# ControlBoardV2_PRO.net
KiCad netlist of a schematic drawn in EAGLE
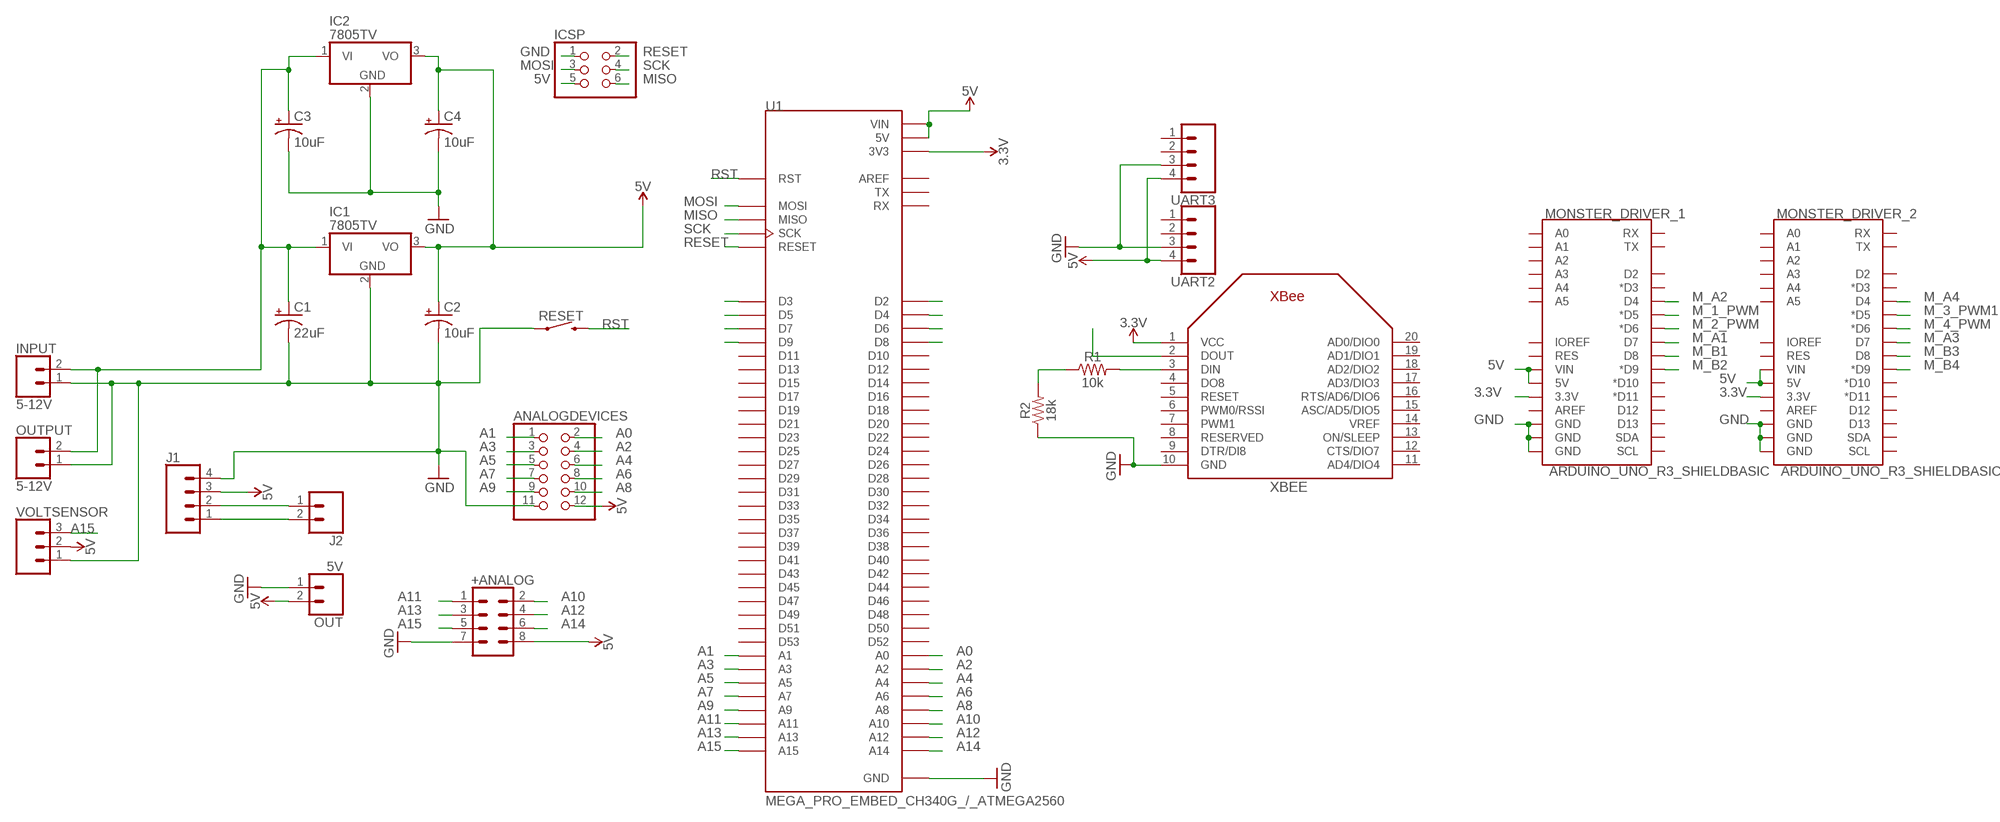
[diagram p0: schematic, sheet 1]

(export (version "E")
  (design (tool "Eeschema 10.0.6"))
  (components
    (comp (ref "+ANALOG")
      (value "CONN_04X2")
      (footprint "eagle-import:2X4")
      (libsource (lib "eagle-import") (part "CONN_04X2"))
    )
    (comp (ref "ANALOGDEVICES")
      (value "PINHD-2X6")
      (footprint "eagle-import:2X06")
      (libsource (lib "eagle-import") (part "PINHD-2X6"))
    )
    (comp (ref "C1")
      (value "22uF")
      (footprint "eagle-import:E2,5-5")
      (libsource (lib "eagle-import") (part "CPOL-USE2.5-5"))
    )
    (comp (ref "C2")
      (value "10uF")
      (footprint "eagle-import:E2,5-5")
      (libsource (lib "eagle-import") (part "CPOL-USE2.5-5"))
    )
    (comp (ref "C3")
      (value "10uF")
      (footprint "eagle-import:E2,5-5")
      (libsource (lib "eagle-import") (part "CPOL-USE2.5-5"))
    )
    (comp (ref "C4")
      (value "10uF")
      (footprint "eagle-import:E2,5-5")
      (libsource (lib "eagle-import") (part "CPOL-USE2.5-5"))
    )
    (comp (ref "IC1")
      (value "7805TV")
      (footprint "eagle-import:TO220V")
      (libsource (lib "eagle-import") (part "78TV05"))
    )
    (comp (ref "IC2")
      (value "7805TV")
      (footprint "eagle-import:TO220V")
      (libsource (lib "eagle-import") (part "78TV05"))
    )
    (comp (ref "ICSP")
      (value "PINHD-2X3")
      (footprint "eagle-import:2X03")
      (libsource (lib "eagle-import") (part "PINHD-2X3"))
    )
    (comp (ref "INPUT")
      (value "5-12V")
      (footprint "eagle-import:SCREWTERMINAL-3.5MM-2")
      (libsource (lib "eagle-import") (part "CONN_023.5MM"))
    )
    (comp (ref "J1")
      (value "CONN_04")
      (footprint "eagle-import:1X04")
      (libsource (lib "eagle-import") (part "CONN_04"))
    )
    (comp (ref "J2")
      (value "CONN_02")
      (footprint "eagle-import:1X02")
      (libsource (lib "eagle-import") (part "CONN_02"))
    )
    (comp (ref "MONSTER_DRIVER_1")
      (value "ARDUINO_UNO_R3_SHIELDBASIC")
      (footprint "eagle-import:UNO_R3_SHIELD")
      (libsource (lib "eagle-import") (part "ARDUINO_UNO_R3_SHIELDBASIC"))
    )
    (comp (ref "MONSTER_DRIVER_2")
      (value "ARDUINO_UNO_R3_SHIELDBASIC")
      (footprint "eagle-import:UNO_R3_SHIELD")
      (libsource (lib "eagle-import") (part "ARDUINO_UNO_R3_SHIELDBASIC"))
    )
    (comp (ref "OUT")
      (value "5V")
      (footprint "eagle-import:SCREWTERMINAL-3.5MM-2")
      (libsource (lib "eagle-import") (part "CONN_023.5MM"))
    )
    (comp (ref "OUTPUT")
      (value "5-12V")
      (footprint "eagle-import:SCREWTERMINAL-3.5MM-2")
      (libsource (lib "eagle-import") (part "CONN_023.5MM"))
    )
    (comp (ref "R1")
      (value "10k")
      (footprint "eagle-import:AXIAL-0.3")
      (libsource (lib "eagle-import") (part "10KOHM-HORIZ-1/4W-1%"))
    )
    (comp (ref "R2")
      (value "18k")
      (footprint "eagle-import:AXIAL-0.3")
      (libsource (lib "eagle-import") (part "10KOHM-HORIZ-1/4W-1%"))
    )
    (comp (ref "RESET")
      (value "MOMENTARY-SWITCH-SPST-PTH-6.0MM")
      (footprint "eagle-import:TACTILE_SWITCH_PTH_6.0MM")
      (libsource (lib "eagle-import") (part "MOMENTARY-SWITCH-SPST-PTH-6.0MM"))
    )
    (comp (ref "U1")
      (value "MEGA_PRO_EMBED_CH340G_/_ATMEGA2560")
      (footprint "eagle-import:MODULE_MEGA_PRO_EMBED_CH340G___ATMEGA2560")
      (fields (field (name "MF") "Robotdyn") (field (name "MP") "Mega Pro Embed CH340G / ATmega2560"))
      (libsource (lib "eagle-import") (part "MEGA_PRO_EMBED_CH340G_/_ATMEGA2560"))
    )
    (comp (ref "UART2")
      (value "CONN_04")
      (footprint "eagle-import:1X04")
      (libsource (lib "eagle-import") (part "CONN_04"))
    )
    (comp (ref "UART3")
      (value "CONN_04")
      (footprint "eagle-import:1X04")
      (libsource (lib "eagle-import") (part "CONN_04"))
    )
    (comp (ref "VOLTSENSOR")
      (value "CONN_03")
      (footprint "eagle-import:1X03")
      (libsource (lib "eagle-import") (part "CONN_03"))
    )
    (comp (ref "XBEE")
      (value "XBEE")
      (footprint "eagle-import:XBEE")
      (libsource (lib "eagle-import") (part "XBEE"))
    )
  )
  (nets
    (net (code "1") (name "/A0") (class "Default")
      (node (ref "ANALOGDEVICES") (pin "2") (pinfunction "2_2") (pintype "passive"))
      (node (ref "U1") (pin "A0") (pinfunction "A0_A0") (pintype "bidirectional"))
    )
    (net (code "2") (name "/A1") (class "Default")
      (node (ref "ANALOGDEVICES") (pin "1") (pinfunction "1_1") (pintype "passive"))
      (node (ref "U1") (pin "A1") (pinfunction "A1_A1") (pintype "bidirectional"))
    )
    (net (code "3") (name "/A2") (class "Default")
      (node (ref "ANALOGDEVICES") (pin "4") (pinfunction "4_4") (pintype "passive"))
      (node (ref "U1") (pin "A2") (pinfunction "A2_A2") (pintype "bidirectional"))
    )
    (net (code "4") (name "/A3") (class "Default")
      (node (ref "ANALOGDEVICES") (pin "3") (pinfunction "3_3") (pintype "passive"))
      (node (ref "U1") (pin "A3") (pinfunction "A3_A3") (pintype "bidirectional"))
    )
    (net (code "5") (name "/A4") (class "Default")
      (node (ref "ANALOGDEVICES") (pin "6") (pinfunction "6_6") (pintype "passive"))
      (node (ref "U1") (pin "A4") (pinfunction "A4_A4") (pintype "bidirectional"))
    )
    (net (code "6") (name "/A5") (class "Default")
      (node (ref "ANALOGDEVICES") (pin "5") (pinfunction "5_5") (pintype "passive"))
      (node (ref "U1") (pin "A5") (pinfunction "A5_A5") (pintype "bidirectional"))
    )
    (net (code "7") (name "/A6") (class "Default")
      (node (ref "ANALOGDEVICES") (pin "8") (pinfunction "8_8") (pintype "passive"))
      (node (ref "U1") (pin "A6") (pinfunction "A6_A6") (pintype "bidirectional"))
    )
    (net (code "8") (name "/A7") (class "Default")
      (node (ref "ANALOGDEVICES") (pin "7") (pinfunction "7_7") (pintype "passive"))
      (node (ref "U1") (pin "A7") (pinfunction "A7_A7") (pintype "bidirectional"))
    )
    (net (code "9") (name "/A8") (class "Default")
      (node (ref "ANALOGDEVICES") (pin "10") (pinfunction "10_10") (pintype "passive"))
      (node (ref "U1") (pin "A8") (pinfunction "A8_A8") (pintype "bidirectional"))
    )
    (net (code "10") (name "/A9") (class "Default")
      (node (ref "ANALOGDEVICES") (pin "9") (pinfunction "9_9") (pintype "passive"))
      (node (ref "U1") (pin "A9") (pinfunction "A9_A9") (pintype "bidirectional"))
    )
    (net (code "11") (name "/A10") (class "Default")
      (node (ref "+ANALOG") (pin "2") (pinfunction "2_2") (pintype "passive"))
      (node (ref "U1") (pin "A10") (pinfunction "A10_A10") (pintype "bidirectional"))
    )
    (net (code "12") (name "/A11") (class "Default")
      (node (ref "+ANALOG") (pin "1") (pinfunction "1_1") (pintype "passive"))
      (node (ref "U1") (pin "A11") (pinfunction "A11_A11") (pintype "bidirectional"))
    )
    (net (code "13") (name "/A12") (class "Default")
      (node (ref "+ANALOG") (pin "4") (pinfunction "4_4") (pintype "passive"))
      (node (ref "U1") (pin "A12") (pinfunction "A12_A12") (pintype "bidirectional"))
    )
    (net (code "14") (name "/A13") (class "Default")
      (node (ref "+ANALOG") (pin "3") (pinfunction "3_3") (pintype "passive"))
      (node (ref "U1") (pin "A13") (pinfunction "A13_A13") (pintype "bidirectional"))
    )
    (net (code "15") (name "/A14") (class "Default")
      (node (ref "+ANALOG") (pin "6") (pinfunction "6_6") (pintype "passive"))
      (node (ref "U1") (pin "A14") (pinfunction "A14_A14") (pintype "bidirectional"))
    )
    (net (code "16") (name "/A15") (class "Default")
      (node (ref "+ANALOG") (pin "5") (pinfunction "5_5") (pintype "passive"))
      (node (ref "U1") (pin "A15") (pinfunction "A15_A15") (pintype "bidirectional"))
      (node (ref "VOLTSENSOR") (pin "3") (pinfunction "3_3") (pintype "passive"))
    )
    (net (code "17") (name "/MISO") (class "Default")
      (node (ref "ICSP") (pin "6") (pinfunction "6_6") (pintype "passive"))
      (node (ref "U1") (pin "MISO") (pinfunction "MISO_MISO") (pintype "bidirectional"))
    )
    (net (code "18") (name "/MOSI") (class "Default")
      (node (ref "ICSP") (pin "3") (pinfunction "3_3") (pintype "passive"))
      (node (ref "U1") (pin "MOSI") (pinfunction "MOSI_MOSI") (pintype "bidirectional"))
    )
    (net (code "19") (name "/M_1_PWM") (class "Default")
      (node (ref "MONSTER_DRIVER_1") (pin "D5") (pinfunction "*D5_D5") (pintype "bidirectional"))
    )
    (net (code "20") (name "/M_2_PWM") (class "Default")
      (node (ref "MONSTER_DRIVER_1") (pin "D6") (pinfunction "*D6_D6") (pintype "bidirectional"))
    )
    (net (code "21") (name "/M_3_PWM1") (class "Default")
      (node (ref "MONSTER_DRIVER_2") (pin "D5") (pinfunction "*D5_D5") (pintype "bidirectional"))
    )
    (net (code "22") (name "/M_4_PWM") (class "Default")
      (node (ref "MONSTER_DRIVER_2") (pin "D6") (pinfunction "*D6_D6") (pintype "bidirectional"))
    )
    (net (code "23") (name "/M_A1") (class "Default")
      (node (ref "MONSTER_DRIVER_1") (pin "D7") (pinfunction "D7_D7") (pintype "bidirectional"))
    )
    (net (code "24") (name "/M_A2") (class "Default")
      (node (ref "MONSTER_DRIVER_1") (pin "D4") (pinfunction "D4_D4") (pintype "bidirectional"))
    )
    (net (code "25") (name "/M_A3") (class "Default")
      (node (ref "MONSTER_DRIVER_2") (pin "D7") (pinfunction "D7_D7") (pintype "bidirectional"))
    )
    (net (code "26") (name "/M_A4") (class "Default")
      (node (ref "MONSTER_DRIVER_2") (pin "D4") (pinfunction "D4_D4") (pintype "bidirectional"))
    )
    (net (code "27") (name "/M_B1") (class "Default")
      (node (ref "MONSTER_DRIVER_1") (pin "D8") (pinfunction "D8_D8") (pintype "bidirectional"))
    )
    (net (code "28") (name "/M_B2") (class "Default")
      (node (ref "MONSTER_DRIVER_1") (pin "D9") (pinfunction "*D9_D9") (pintype "bidirectional"))
    )
    (net (code "29") (name "/M_B3") (class "Default")
      (node (ref "MONSTER_DRIVER_2") (pin "D8") (pinfunction "D8_D8") (pintype "bidirectional"))
    )
    (net (code "30") (name "/M_B4") (class "Default")
      (node (ref "MONSTER_DRIVER_2") (pin "D9") (pinfunction "*D9_D9") (pintype "bidirectional"))
    )
    (net (code "31") (name "/RESET") (class "Default")
      (node (ref "ICSP") (pin "2") (pinfunction "2_2") (pintype "passive"))
      (node (ref "U1") (pin "RESET") (pinfunction "RESET_RESET") (pintype "input"))
    )
    (net (code "32") (name "/RST") (class "Default")
      (node (ref "RESET") (pin "3") (pinfunction "2_3") (pintype "passive"))
      (node (ref "U1") (pin "RST") (pinfunction "RST_RST") (pintype "input"))
    )
    (net (code "33") (name "/SCK") (class "Default")
      (node (ref "ICSP") (pin "4") (pinfunction "4_4") (pintype "passive"))
      (node (ref "U1") (pin "SCK") (pinfunction "SCK_SCK") (pintype "bidirectional"))
    )
    (net (code "34") (name "3.3V") (class "Default")
      (node (ref "MONSTER_DRIVER_1") (pin "3.3V") (pinfunction "3.3V_3.3V") (pintype "bidirectional"))
      (node (ref "MONSTER_DRIVER_2") (pin "3.3V") (pinfunction "3.3V_3.3V") (pintype "bidirectional"))
      (node (ref "U1") (pin "3V3_1") (pinfunction "3V3_3V3_1") (pintype "power_in"))
      (node (ref "U1") (pin "3V3_2") (pinfunction "3V3_3V3_2") (pintype "power_in"))
      (node (ref "XBEE") (pin "1") (pinfunction "VCC_1") (pintype "power_in"))
    )
    (net (code "35") (name "5V") (class "Default")
      (node (ref "+ANALOG") (pin "8") (pinfunction "8_8") (pintype "passive"))
      (node (ref "ANALOGDEVICES") (pin "12") (pinfunction "12_12") (pintype "passive"))
      (node (ref "C2") (pin "+") (pinfunction "+_+") (pintype "passive"))
      (node (ref "C4") (pin "+") (pinfunction "+_+") (pintype "passive"))
      (node (ref "IC1") (pin "3") (pinfunction "VO_3") (pintype "passive"))
      (node (ref "IC2") (pin "3") (pinfunction "VO_3") (pintype "passive"))
      (node (ref "ICSP") (pin "5") (pinfunction "5_5") (pintype "passive"))
      (node (ref "J1") (pin "3") (pinfunction "3_3") (pintype "passive"))
      (node (ref "MONSTER_DRIVER_1") (pin "5V") (pinfunction "5V_5V") (pintype "bidirectional"))
      (node (ref "MONSTER_DRIVER_1") (pin "VIN") (pinfunction "VIN_VIN") (pintype "bidirectional"))
      (node (ref "MONSTER_DRIVER_2") (pin "5V") (pinfunction "5V_5V") (pintype "bidirectional"))
      (node (ref "MONSTER_DRIVER_2") (pin "VIN") (pinfunction "VIN_VIN") (pintype "bidirectional"))
      (node (ref "OUT") (pin "2") (pinfunction "2_2") (pintype "passive"))
      (node (ref "U1") (pin "5V_1") (pinfunction "5V_5V_1") (pintype "power_in"))
      (node (ref "U1") (pin "5V_2") (pinfunction "5V_5V_2") (pintype "power_in"))
      (node (ref "U1") (pin "5V_3") (pinfunction "5V_5V_3") (pintype "power_in"))
      (node (ref "U1") (pin "VIN_1") (pinfunction "VIN_VIN_1") (pintype "power_in"))
      (node (ref "U1") (pin "VIN_2") (pinfunction "VIN_VIN_2") (pintype "power_in"))
      (node (ref "UART2") (pin "4") (pinfunction "4_4") (pintype "passive"))
      (node (ref "UART3") (pin "4") (pinfunction "4_4") (pintype "passive"))
      (node (ref "VOLTSENSOR") (pin "2") (pinfunction "2_2") (pintype "passive"))
    )
    (net (code "36") (name "GND") (class "Default")
      (node (ref "+ANALOG") (pin "7") (pinfunction "7_7") (pintype "passive"))
      (node (ref "ANALOGDEVICES") (pin "11") (pinfunction "11_11") (pintype "passive"))
      (node (ref "C1") (pin "-") (pinfunction "-_-") (pintype "passive"))
      (node (ref "C2") (pin "-") (pinfunction "-_-") (pintype "passive"))
      (node (ref "C3") (pin "-") (pinfunction "-_-") (pintype "passive"))
      (node (ref "C4") (pin "-") (pinfunction "-_-") (pintype "passive"))
      (node (ref "IC1") (pin "2") (pinfunction "GND_2") (pintype "passive"))
      (node (ref "IC2") (pin "2") (pinfunction "GND_2") (pintype "passive"))
      (node (ref "ICSP") (pin "1") (pinfunction "1_1") (pintype "passive"))
      (node (ref "INPUT") (pin "1") (pinfunction "1_1") (pintype "passive"))
      (node (ref "J1") (pin "4") (pinfunction "4_4") (pintype "passive"))
      (node (ref "MONSTER_DRIVER_1") (pin "GND@0") (pinfunction "GND_GND@0") (pintype "bidirectional"))
      (node (ref "MONSTER_DRIVER_1") (pin "GND@1") (pinfunction "GND_GND@1") (pintype "bidirectional"))
      (node (ref "MONSTER_DRIVER_1") (pin "GND@2") (pinfunction "GND_GND@2") (pintype "bidirectional"))
      (node (ref "MONSTER_DRIVER_2") (pin "GND@0") (pinfunction "GND_GND@0") (pintype "bidirectional"))
      (node (ref "MONSTER_DRIVER_2") (pin "GND@1") (pinfunction "GND_GND@1") (pintype "bidirectional"))
      (node (ref "MONSTER_DRIVER_2") (pin "GND@2") (pinfunction "GND_GND@2") (pintype "bidirectional"))
      (node (ref "OUT") (pin "1") (pinfunction "1_1") (pintype "passive"))
      (node (ref "OUTPUT") (pin "1") (pinfunction "1_1") (pintype "passive"))
      (node (ref "R2") (pin "P$1") (pinfunction "1_P$1") (pintype "passive"))
      (node (ref "RESET") (pin "1") (pinfunction "1_1") (pintype "passive"))
      (node (ref "U1") (pin "GND_1") (pinfunction "GND_GND_1") (pintype "power_in"))
      (node (ref "U1") (pin "GND_2") (pinfunction "GND_GND_2") (pintype "power_in"))
      (node (ref "U1") (pin "GND_3") (pinfunction "GND_GND_3") (pintype "power_in"))
      (node (ref "UART2") (pin "3") (pinfunction "3_3") (pintype "passive"))
      (node (ref "UART3") (pin "3") (pinfunction "3_3") (pintype "passive"))
      (node (ref "VOLTSENSOR") (pin "1") (pinfunction "1_1") (pintype "passive"))
      (node (ref "XBEE") (pin "10") (pinfunction "GND_10") (pintype "power_in"))
    )
    (net (code "37") (name "Net-(IC1-VI)") (class "Default")
      (node (ref "C1") (pin "+") (pinfunction "+_+") (pintype "passive"))
      (node (ref "C3") (pin "+") (pinfunction "+_+") (pintype "passive"))
      (node (ref "IC1") (pin "1") (pinfunction "VI_1") (pintype "input"))
      (node (ref "IC2") (pin "1") (pinfunction "VI_1") (pintype "input"))
      (node (ref "INPUT") (pin "2") (pinfunction "2_2") (pintype "passive"))
      (node (ref "OUTPUT") (pin "2") (pinfunction "2_2") (pintype "passive"))
    )
    (net (code "38") (name "Net-(J1-Pad1)") (class "Default")
      (node (ref "J1") (pin "1") (pinfunction "1_1") (pintype "passive"))
      (node (ref "J2") (pin "2") (pinfunction "2_2") (pintype "passive"))
    )
    (net (code "39") (name "Net-(J1-Pad2)") (class "Default")
      (node (ref "J1") (pin "2") (pinfunction "2_2") (pintype "passive"))
      (node (ref "J2") (pin "1") (pinfunction "1_1") (pintype "passive"))
    )
    (net (code "40") (name "Net-(R1-1)") (class "Default")
      (node (ref "R1") (pin "P$1") (pinfunction "1_P$1") (pintype "passive"))
      (node (ref "R2") (pin "P$2") (pinfunction "2_P$2") (pintype "passive"))
    )
    (net (code "41") (name "Net-(R1-2)") (class "Default")
      (node (ref "R1") (pin "P$2") (pinfunction "2_P$2") (pintype "passive"))
      (node (ref "XBEE") (pin "3") (pinfunction "DIN_3") (pintype "input"))
    )
    (net (code "42") (name "unconnected-(MONSTER_DRIVER_1-*D3-PadD3)") (class "Default")
      (node (ref "MONSTER_DRIVER_1") (pin "D3") (pinfunction "*D3_D3") (pintype "bidirectional"))
    )
    (net (code "43") (name "unconnected-(MONSTER_DRIVER_1-*D10-PadD10)") (class "Default")
      (node (ref "MONSTER_DRIVER_1") (pin "D10") (pinfunction "*D10_D10") (pintype "bidirectional"))
    )
    (net (code "44") (name "unconnected-(MONSTER_DRIVER_1-*D11-PadD11)") (class "Default")
      (node (ref "MONSTER_DRIVER_1") (pin "D11") (pinfunction "*D11_D11") (pintype "bidirectional"))
    )
    (net (code "45") (name "unconnected-(MONSTER_DRIVER_1-PadA0)") (class "Default")
      (node (ref "MONSTER_DRIVER_1") (pin "A0") (pinfunction "A0_A0") (pintype "bidirectional"))
    )
    (net (code "46") (name "unconnected-(MONSTER_DRIVER_1-PadA1)") (class "Default")
      (node (ref "MONSTER_DRIVER_1") (pin "A1") (pinfunction "A1_A1") (pintype "bidirectional"))
    )
    (net (code "47") (name "unconnected-(MONSTER_DRIVER_1-PadA2)") (class "Default")
      (node (ref "MONSTER_DRIVER_1") (pin "A2") (pinfunction "A2_A2") (pintype "bidirectional"))
    )
    (net (code "48") (name "unconnected-(MONSTER_DRIVER_1-PadA3)") (class "Default")
      (node (ref "MONSTER_DRIVER_1") (pin "A3") (pinfunction "A3_A3") (pintype "bidirectional"))
    )
    (net (code "49") (name "unconnected-(MONSTER_DRIVER_1-PadA4)") (class "Default")
      (node (ref "MONSTER_DRIVER_1") (pin "A4") (pinfunction "A4_A4") (pintype "bidirectional"))
    )
    (net (code "50") (name "unconnected-(MONSTER_DRIVER_1-PadA5)") (class "Default")
      (node (ref "MONSTER_DRIVER_1") (pin "A5") (pinfunction "A5_A5") (pintype "bidirectional"))
    )
    (net (code "51") (name "unconnected-(MONSTER_DRIVER_1-PadAREF)") (class "Default")
      (node (ref "MONSTER_DRIVER_1") (pin "AREF") (pinfunction "AREF_AREF") (pintype "bidirectional"))
    )
    (net (code "52") (name "unconnected-(MONSTER_DRIVER_1-PadD2)") (class "Default")
      (node (ref "MONSTER_DRIVER_1") (pin "D2") (pinfunction "D2_D2") (pintype "bidirectional"))
    )
    (net (code "53") (name "unconnected-(MONSTER_DRIVER_1-PadD12)") (class "Default")
      (node (ref "MONSTER_DRIVER_1") (pin "D12") (pinfunction "D12_D12") (pintype "bidirectional"))
    )
    (net (code "54") (name "unconnected-(MONSTER_DRIVER_1-PadD13)") (class "Default")
      (node (ref "MONSTER_DRIVER_1") (pin "D13") (pinfunction "D13_D13") (pintype "bidirectional"))
    )
    (net (code "55") (name "unconnected-(MONSTER_DRIVER_1-PadIOREF)") (class "Default")
      (node (ref "MONSTER_DRIVER_1") (pin "IOREF") (pinfunction "IOREF_IOREF") (pintype "bidirectional"))
    )
    (net (code "56") (name "unconnected-(MONSTER_DRIVER_1-PadRES)") (class "Default")
      (node (ref "MONSTER_DRIVER_1") (pin "RES") (pinfunction "RES_RES") (pintype "bidirectional"))
    )
    (net (code "57") (name "unconnected-(MONSTER_DRIVER_1-PadRX)") (class "Default")
      (node (ref "MONSTER_DRIVER_1") (pin "RX") (pinfunction "RX_RX") (pintype "bidirectional"))
    )
    (net (code "58") (name "unconnected-(MONSTER_DRIVER_1-PadSCL)") (class "Default")
      (node (ref "MONSTER_DRIVER_1") (pin "SCL") (pinfunction "SCL_SCL") (pintype "bidirectional"))
    )
    (net (code "59") (name "unconnected-(MONSTER_DRIVER_1-PadSDA)") (class "Default")
      (node (ref "MONSTER_DRIVER_1") (pin "SDA") (pinfunction "SDA_SDA") (pintype "bidirectional"))
    )
    (net (code "60") (name "unconnected-(MONSTER_DRIVER_1-PadTX)") (class "Default")
      (node (ref "MONSTER_DRIVER_1") (pin "TX") (pinfunction "TX_TX") (pintype "bidirectional"))
    )
    (net (code "61") (name "unconnected-(MONSTER_DRIVER_2-*D3-PadD3)") (class "Default")
      (node (ref "MONSTER_DRIVER_2") (pin "D3") (pinfunction "*D3_D3") (pintype "bidirectional"))
    )
    (net (code "62") (name "unconnected-(MONSTER_DRIVER_2-*D10-PadD10)") (class "Default")
      (node (ref "MONSTER_DRIVER_2") (pin "D10") (pinfunction "*D10_D10") (pintype "bidirectional"))
    )
    (net (code "63") (name "unconnected-(MONSTER_DRIVER_2-*D11-PadD11)") (class "Default")
      (node (ref "MONSTER_DRIVER_2") (pin "D11") (pinfunction "*D11_D11") (pintype "bidirectional"))
    )
    (net (code "64") (name "unconnected-(MONSTER_DRIVER_2-PadA0)") (class "Default")
      (node (ref "MONSTER_DRIVER_2") (pin "A0") (pinfunction "A0_A0") (pintype "bidirectional"))
    )
    (net (code "65") (name "unconnected-(MONSTER_DRIVER_2-PadA1)") (class "Default")
      (node (ref "MONSTER_DRIVER_2") (pin "A1") (pinfunction "A1_A1") (pintype "bidirectional"))
    )
    (net (code "66") (name "unconnected-(MONSTER_DRIVER_2-PadA2)") (class "Default")
      (node (ref "MONSTER_DRIVER_2") (pin "A2") (pinfunction "A2_A2") (pintype "bidirectional"))
    )
    (net (code "67") (name "unconnected-(MONSTER_DRIVER_2-PadA3)") (class "Default")
      (node (ref "MONSTER_DRIVER_2") (pin "A3") (pinfunction "A3_A3") (pintype "bidirectional"))
    )
    (net (code "68") (name "unconnected-(MONSTER_DRIVER_2-PadA4)") (class "Default")
      (node (ref "MONSTER_DRIVER_2") (pin "A4") (pinfunction "A4_A4") (pintype "bidirectional"))
    )
    (net (code "69") (name "unconnected-(MONSTER_DRIVER_2-PadA5)") (class "Default")
      (node (ref "MONSTER_DRIVER_2") (pin "A5") (pinfunction "A5_A5") (pintype "bidirectional"))
    )
    (net (code "70") (name "unconnected-(MONSTER_DRIVER_2-PadAREF)") (class "Default")
      (node (ref "MONSTER_DRIVER_2") (pin "AREF") (pinfunction "AREF_AREF") (pintype "bidirectional"))
    )
    (net (code "71") (name "unconnected-(MONSTER_DRIVER_2-PadD2)") (class "Default")
      (node (ref "MONSTER_DRIVER_2") (pin "D2") (pinfunction "D2_D2") (pintype "bidirectional"))
    )
    (net (code "72") (name "unconnected-(MONSTER_DRIVER_2-PadD12)") (class "Default")
      (node (ref "MONSTER_DRIVER_2") (pin "D12") (pinfunction "D12_D12") (pintype "bidirectional"))
    )
    (net (code "73") (name "unconnected-(MONSTER_DRIVER_2-PadD13)") (class "Default")
      (node (ref "MONSTER_DRIVER_2") (pin "D13") (pinfunction "D13_D13") (pintype "bidirectional"))
    )
    (net (code "74") (name "unconnected-(MONSTER_DRIVER_2-PadIOREF)") (class "Default")
      (node (ref "MONSTER_DRIVER_2") (pin "IOREF") (pinfunction "IOREF_IOREF") (pintype "bidirectional"))
    )
    (net (code "75") (name "unconnected-(MONSTER_DRIVER_2-PadRES)") (class "Default")
      (node (ref "MONSTER_DRIVER_2") (pin "RES") (pinfunction "RES_RES") (pintype "bidirectional"))
    )
    (net (code "76") (name "unconnected-(MONSTER_DRIVER_2-PadRX)") (class "Default")
      (node (ref "MONSTER_DRIVER_2") (pin "RX") (pinfunction "RX_RX") (pintype "bidirectional"))
    )
    (net (code "77") (name "unconnected-(MONSTER_DRIVER_2-PadSCL)") (class "Default")
      (node (ref "MONSTER_DRIVER_2") (pin "SCL") (pinfunction "SCL_SCL") (pintype "bidirectional"))
    )
    (net (code "78") (name "unconnected-(MONSTER_DRIVER_2-PadSDA)") (class "Default")
      (node (ref "MONSTER_DRIVER_2") (pin "SDA") (pinfunction "SDA_SDA") (pintype "bidirectional"))
    )
    (net (code "79") (name "unconnected-(MONSTER_DRIVER_2-PadTX)") (class "Default")
      (node (ref "MONSTER_DRIVER_2") (pin "TX") (pinfunction "TX_TX") (pintype "bidirectional"))
    )
    (net (code "80") (name "unconnected-(U1-PadAREF)") (class "Default")
      (node (ref "U1") (pin "AREF") (pinfunction "AREF_AREF") (pintype "bidirectional"))
    )
    (net (code "81") (name "unconnected-(U1-PadD2)") (class "Default")
      (node (ref "U1") (pin "D2") (pinfunction "D2_D2") (pintype "bidirectional"))
    )
    (net (code "82") (name "unconnected-(U1-PadD3)") (class "Default")
      (node (ref "U1") (pin "D3") (pinfunction "D3_D3") (pintype "bidirectional"))
    )
    (net (code "83") (name "unconnected-(U1-PadD4)") (class "Default")
      (node (ref "U1") (pin "D4") (pinfunction "D4_D4") (pintype "bidirectional"))
    )
    (net (code "84") (name "unconnected-(U1-PadD5)") (class "Default")
      (node (ref "U1") (pin "D5") (pinfunction "D5_D5") (pintype "bidirectional"))
    )
    (net (code "85") (name "unconnected-(U1-PadD6)") (class "Default")
      (node (ref "U1") (pin "D6") (pinfunction "D6_D6") (pintype "bidirectional"))
    )
    (net (code "86") (name "unconnected-(U1-PadD7)") (class "Default")
      (node (ref "U1") (pin "D7") (pinfunction "D7_D7") (pintype "bidirectional"))
    )
    (net (code "87") (name "unconnected-(U1-PadD8)") (class "Default")
      (node (ref "U1") (pin "D8") (pinfunction "D8_D8") (pintype "bidirectional"))
    )
    (net (code "88") (name "unconnected-(U1-PadD9)") (class "Default")
      (node (ref "U1") (pin "D9") (pinfunction "D9_D9") (pintype "bidirectional"))
    )
    (net (code "89") (name "unconnected-(U1-PadD10)") (class "Default")
      (node (ref "U1") (pin "D10") (pinfunction "D10_D10") (pintype "bidirectional"))
    )
    (net (code "90") (name "unconnected-(U1-PadD11)") (class "Default")
      (node (ref "U1") (pin "D11") (pinfunction "D11_D11") (pintype "bidirectional"))
    )
    (net (code "91") (name "unconnected-(U1-PadD12)") (class "Default")
      (node (ref "U1") (pin "D12") (pinfunction "D12_D12") (pintype "bidirectional"))
    )
    (net (code "92") (name "unconnected-(U1-PadD13)") (class "Default")
      (node (ref "U1") (pin "D13") (pinfunction "D13_D13") (pintype "bidirectional"))
    )
    (net (code "93") (name "unconnected-(U1-PadD14)") (class "Default")
      (node (ref "U1") (pin "D14") (pinfunction "D14_D14") (pintype "bidirectional"))
    )
    (net (code "94") (name "unconnected-(U1-PadD15)") (class "Default")
      (node (ref "U1") (pin "D15") (pinfunction "D15_D15") (pintype "bidirectional"))
    )
    (net (code "95") (name "unconnected-(U1-PadD16)") (class "Default")
      (node (ref "U1") (pin "D16") (pinfunction "D16_D16") (pintype "bidirectional"))
    )
    (net (code "96") (name "unconnected-(U1-PadD17)") (class "Default")
      (node (ref "U1") (pin "D17") (pinfunction "D17_D17") (pintype "bidirectional"))
    )
    (net (code "97") (name "unconnected-(U1-PadD18)") (class "Default")
      (node (ref "U1") (pin "D18") (pinfunction "D18_D18") (pintype "bidirectional"))
    )
    (net (code "98") (name "unconnected-(U1-PadD19)") (class "Default")
      (node (ref "U1") (pin "D19") (pinfunction "D19_D19") (pintype "bidirectional"))
    )
    (net (code "99") (name "unconnected-(U1-PadD20)") (class "Default")
      (node (ref "U1") (pin "D20") (pinfunction "D20_D20") (pintype "bidirectional"))
    )
    (net (code "100") (name "unconnected-(U1-PadD21)") (class "Default")
      (node (ref "U1") (pin "D21") (pinfunction "D21_D21") (pintype "bidirectional"))
    )
    (net (code "101") (name "unconnected-(U1-PadD22)") (class "Default")
      (node (ref "U1") (pin "D22") (pinfunction "D22_D22") (pintype "bidirectional"))
    )
    (net (code "102") (name "unconnected-(U1-PadD23)") (class "Default")
      (node (ref "U1") (pin "D23") (pinfunction "D23_D23") (pintype "bidirectional"))
    )
    (net (code "103") (name "unconnected-(U1-PadD24)") (class "Default")
      (node (ref "U1") (pin "D24") (pinfunction "D24_D24") (pintype "bidirectional"))
    )
    (net (code "104") (name "unconnected-(U1-PadD25)") (class "Default")
      (node (ref "U1") (pin "D25") (pinfunction "D25_D25") (pintype "bidirectional"))
    )
    (net (code "105") (name "unconnected-(U1-PadD26)") (class "Default")
      (node (ref "U1") (pin "D26") (pinfunction "D26_D26") (pintype "bidirectional"))
    )
    (net (code "106") (name "unconnected-(U1-PadD27)") (class "Default")
      (node (ref "U1") (pin "D27") (pinfunction "D27_D27") (pintype "bidirectional"))
    )
    (net (code "107") (name "unconnected-(U1-PadD28)") (class "Default")
      (node (ref "U1") (pin "D28") (pinfunction "D28_D28") (pintype "bidirectional"))
    )
    (net (code "108") (name "unconnected-(U1-PadD29)") (class "Default")
      (node (ref "U1") (pin "D29") (pinfunction "D29_D29") (pintype "bidirectional"))
    )
    (net (code "109") (name "unconnected-(U1-PadD30)") (class "Default")
      (node (ref "U1") (pin "D30") (pinfunction "D30_D30") (pintype "bidirectional"))
    )
    (net (code "110") (name "unconnected-(U1-PadD31)") (class "Default")
      (node (ref "U1") (pin "D31") (pinfunction "D31_D31") (pintype "bidirectional"))
    )
    (net (code "111") (name "unconnected-(U1-PadD32)") (class "Default")
      (node (ref "U1") (pin "D32") (pinfunction "D32_D32") (pintype "bidirectional"))
    )
    (net (code "112") (name "unconnected-(U1-PadD33)") (class "Default")
      (node (ref "U1") (pin "D33") (pinfunction "D33_D33") (pintype "bidirectional"))
    )
    (net (code "113") (name "unconnected-(U1-PadD34)") (class "Default")
      (node (ref "U1") (pin "D34") (pinfunction "D34_D34") (pintype "bidirectional"))
    )
    (net (code "114") (name "unconnected-(U1-PadD35)") (class "Default")
      (node (ref "U1") (pin "D35") (pinfunction "D35_D35") (pintype "bidirectional"))
    )
    (net (code "115") (name "unconnected-(U1-PadD36)") (class "Default")
      (node (ref "U1") (pin "D36") (pinfunction "D36_D36") (pintype "bidirectional"))
    )
    (net (code "116") (name "unconnected-(U1-PadD37)") (class "Default")
      (node (ref "U1") (pin "D37") (pinfunction "D37_D37") (pintype "bidirectional"))
    )
    (net (code "117") (name "unconnected-(U1-PadD38)") (class "Default")
      (node (ref "U1") (pin "D38") (pinfunction "D38_D38") (pintype "bidirectional"))
    )
    (net (code "118") (name "unconnected-(U1-PadD39)") (class "Default")
      (node (ref "U1") (pin "D39") (pinfunction "D39_D39") (pintype "bidirectional"))
    )
    (net (code "119") (name "unconnected-(U1-PadD40)") (class "Default")
      (node (ref "U1") (pin "D40") (pinfunction "D40_D40") (pintype "bidirectional"))
    )
    (net (code "120") (name "unconnected-(U1-PadD41)") (class "Default")
      (node (ref "U1") (pin "D41") (pinfunction "D41_D41") (pintype "bidirectional"))
    )
    (net (code "121") (name "unconnected-(U1-PadD42)") (class "Default")
      (node (ref "U1") (pin "D42") (pinfunction "D42_D42") (pintype "bidirectional"))
    )
    (net (code "122") (name "unconnected-(U1-PadD43)") (class "Default")
      (node (ref "U1") (pin "D43") (pinfunction "D43_D43") (pintype "bidirectional"))
    )
    (net (code "123") (name "unconnected-(U1-PadD44)") (class "Default")
      (node (ref "U1") (pin "D44") (pinfunction "D44_D44") (pintype "bidirectional"))
    )
    (net (code "124") (name "unconnected-(U1-PadD45)") (class "Default")
      (node (ref "U1") (pin "D45") (pinfunction "D45_D45") (pintype "bidirectional"))
    )
    (net (code "125") (name "unconnected-(U1-PadD46)") (class "Default")
      (node (ref "U1") (pin "D46") (pinfunction "D46_D46") (pintype "bidirectional"))
    )
    (net (code "126") (name "unconnected-(U1-PadD47)") (class "Default")
      (node (ref "U1") (pin "D47") (pinfunction "D47_D47") (pintype "bidirectional"))
    )
    (net (code "127") (name "unconnected-(U1-PadD48)") (class "Default")
      (node (ref "U1") (pin "D48") (pinfunction "D48_D48") (pintype "bidirectional"))
    )
    (net (code "128") (name "unconnected-(U1-PadD49)") (class "Default")
      (node (ref "U1") (pin "D49") (pinfunction "D49_D49") (pintype "bidirectional"))
    )
    (net (code "129") (name "unconnected-(U1-PadD50)") (class "Default")
      (node (ref "U1") (pin "D50") (pinfunction "D50_D50") (pintype "bidirectional"))
    )
    (net (code "130") (name "unconnected-(U1-PadD51)") (class "Default")
      (node (ref "U1") (pin "D51") (pinfunction "D51_D51") (pintype "bidirectional"))
    )
    (net (code "131") (name "unconnected-(U1-PadD52)") (class "Default")
      (node (ref "U1") (pin "D52") (pinfunction "D52_D52") (pintype "bidirectional"))
    )
    (net (code "132") (name "unconnected-(U1-PadD53)") (class "Default")
      (node (ref "U1") (pin "D53") (pinfunction "D53_D53") (pintype "bidirectional"))
    )
    (net (code "133") (name "unconnected-(U1-PadRX)") (class "Default")
      (node (ref "U1") (pin "RX") (pinfunction "RX_RX") (pintype "input"))
    )
    (net (code "134") (name "unconnected-(U1-PadTX)") (class "Default")
      (node (ref "U1") (pin "TX") (pinfunction "TX_TX") (pintype "output"))
    )
    (net (code "135") (name "unconnected-(UART2-Pad1)") (class "Default")
      (node (ref "UART2") (pin "1") (pinfunction "1_1") (pintype "passive"))
    )
    (net (code "136") (name "unconnected-(UART2-Pad2)") (class "Default")
      (node (ref "UART2") (pin "2") (pinfunction "2_2") (pintype "passive"))
    )
    (net (code "137") (name "unconnected-(UART3-Pad1)") (class "Default")
      (node (ref "UART3") (pin "1") (pinfunction "1_1") (pintype "passive"))
    )
    (net (code "138") (name "unconnected-(UART3-Pad2)") (class "Default")
      (node (ref "UART3") (pin "2") (pinfunction "2_2") (pintype "passive"))
    )
    (net (code "139") (name "unconnected-(XBEE-AD0{slash}DIO0-Pad20)") (class "Default")
      (node (ref "XBEE") (pin "20") (pinfunction "AD0/DIO0_20") (pintype "bidirectional"))
    )
    (net (code "140") (name "unconnected-(XBEE-AD1{slash}DIO1-Pad19)") (class "Default")
      (node (ref "XBEE") (pin "19") (pinfunction "AD1/DIO1_19") (pintype "bidirectional"))
    )
    (net (code "141") (name "unconnected-(XBEE-AD2{slash}DIO2-Pad18)") (class "Default")
      (node (ref "XBEE") (pin "18") (pinfunction "AD2/DIO2_18") (pintype "bidirectional"))
    )
    (net (code "142") (name "unconnected-(XBEE-AD3{slash}DIO3-Pad17)") (class "Default")
      (node (ref "XBEE") (pin "17") (pinfunction "AD3/DIO3_17") (pintype "bidirectional"))
    )
    (net (code "143") (name "unconnected-(XBEE-AD4{slash}DIO4-Pad11)") (class "Default")
      (node (ref "XBEE") (pin "11") (pinfunction "AD4/DIO4_11") (pintype "bidirectional"))
    )
    (net (code "144") (name "unconnected-(XBEE-ASC{slash}AD5{slash}DIO5-Pad15)") (class "Default")
      (node (ref "XBEE") (pin "15") (pinfunction "ASC/AD5/DIO5_15") (pintype "bidirectional"))
    )
    (net (code "145") (name "unconnected-(XBEE-CTS{slash}DIO7-Pad12)") (class "Default")
      (node (ref "XBEE") (pin "12") (pinfunction "CTS/DIO7_12") (pintype "bidirectional"))
    )
    (net (code "146") (name "unconnected-(XBEE-DO8-Pad4)") (class "Default")
      (node (ref "XBEE") (pin "4") (pinfunction "DO8_4") (pintype "output"))
    )
    (net (code "147") (name "unconnected-(XBEE-DOUT-Pad2)") (class "Default")
      (node (ref "XBEE") (pin "2") (pinfunction "DOUT_2") (pintype "output"))
    )
    (net (code "148") (name "unconnected-(XBEE-DTR{slash}DI8-Pad9)") (class "Default")
      (node (ref "XBEE") (pin "9") (pinfunction "DTR/DI8_9") (pintype "input"))
    )
    (net (code "149") (name "unconnected-(XBEE-ON{slash}SLEEP-Pad13)") (class "Default")
      (node (ref "XBEE") (pin "13") (pinfunction "ON/SLEEP_13") (pintype "output"))
    )
    (net (code "150") (name "unconnected-(XBEE-PWM0{slash}RSSI-Pad6)") (class "Default")
      (node (ref "XBEE") (pin "6") (pinfunction "PWM0/RSSI_6") (pintype "output"))
    )
    (net (code "151") (name "unconnected-(XBEE-PWM1-Pad7)") (class "Default")
      (node (ref "XBEE") (pin "7") (pinfunction "PWM1_7") (pintype "output"))
    )
    (net (code "152") (name "unconnected-(XBEE-RESERVED-Pad8)") (class "Default")
      (node (ref "XBEE") (pin "8") (pinfunction "RESERVED_8") (pintype "no_connect"))
    )
    (net (code "153") (name "unconnected-(XBEE-RESET-Pad5)") (class "Default")
      (node (ref "XBEE") (pin "5") (pinfunction "RESET_5") (pintype "input"))
    )
    (net (code "154") (name "unconnected-(XBEE-RTS{slash}AD6{slash}DIO6-Pad16)") (class "Default")
      (node (ref "XBEE") (pin "16") (pinfunction "RTS/AD6/DIO6_16") (pintype "bidirectional"))
    )
    (net (code "155") (name "unconnected-(XBEE-VREF-Pad14)") (class "Default")
      (node (ref "XBEE") (pin "14") (pinfunction "VREF_14") (pintype "input"))
    )
  )
)
